# Statemachine_ST7735.net
KiCad netlist of a schematic drawn in EAGLE
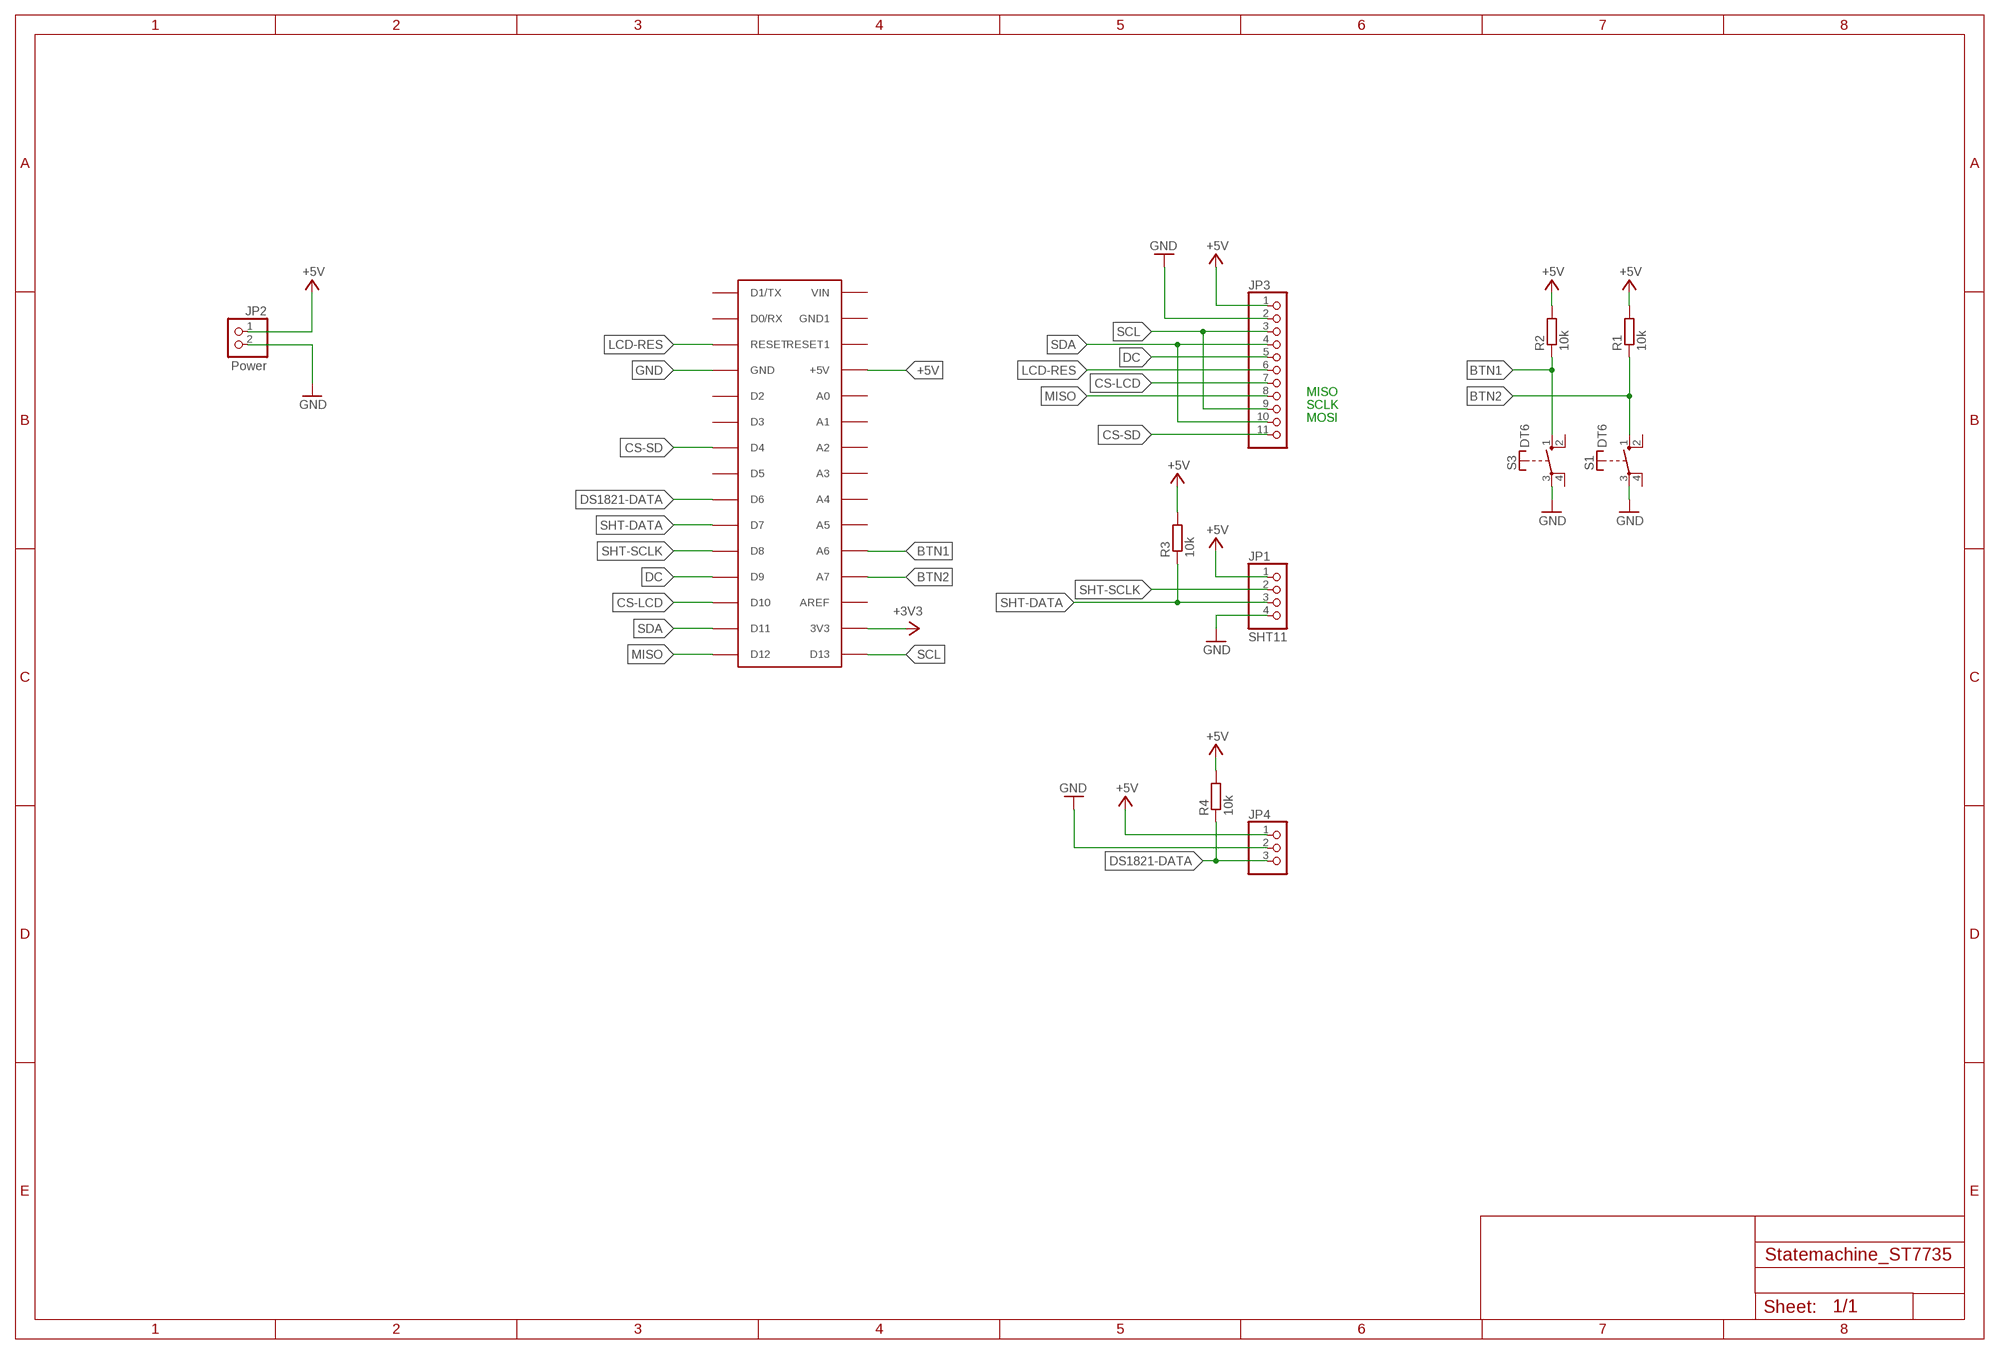
[diagram p0: schematic, sheet 1]

(export (version "E")
  (design (tool "Eeschema 10.0.6"))
  (components
    (comp (ref "JP1")
      (value "SHT11")
      (footprint "eagle-import:1X04")
      (libsource (lib "eagle-import") (part "PINHD-1X4"))
    )
    (comp (ref "JP2")
      (value "Power")
      (footprint "eagle-import:1X02")
      (libsource (lib "eagle-import") (part "PINHD-1X2"))
    )
    (comp (ref "JP3")
      (value "PINHD-1X11")
      (footprint "eagle-import:1X11")
      (libsource (lib "eagle-import") (part "PINHD-1X11"))
    )
    (comp (ref "JP4")
      (value "PINHD-1X3")
      (footprint "eagle-import:1X03")
      (libsource (lib "eagle-import") (part "PINHD-1X3"))
    )
    (comp (ref "R1")
      (value "10k")
      (footprint "eagle-import:0207_10")
      (libsource (lib "eagle-import") (part "R-EU_0207/10"))
    )
    (comp (ref "R2")
      (value "10k")
      (footprint "eagle-import:0204_7")
      (libsource (lib "eagle-import") (part "R-EU_0204/7"))
    )
    (comp (ref "R3")
      (value "10k")
      (footprint "eagle-import:0204_7")
      (libsource (lib "eagle-import") (part "R-EU_0204/7"))
    )
    (comp (ref "R4")
      (value "10k")
      (footprint "eagle-import:0207_10")
      (libsource (lib "eagle-import") (part "R-EU_0207/10"))
    )
    (comp (ref "S1")
      (value "DT6")
      (footprint "eagle-import:DT6")
      (libsource (lib "eagle-import") (part "DT6"))
    )
    (comp (ref "S3")
      (value "DT6")
      (footprint "eagle-import:DT6")
      (libsource (lib "eagle-import") (part "DT6"))
    )
    (comp (ref "U$1")
      (value "ARDUINONANO")
      (footprint "eagle-import:PDIP-32")
      (libsource (lib "eagle-import") (part "ARDUINONANO"))
    )
  )
  (nets
    (net (code "1") (name "+3V3") (class "Default")
      (node (ref "U$1") (pin "3V3") (pinfunction "3V3_3V3") (pintype "bidirectional"))
    )
    (net (code "2") (name "+5V") (class "Default")
      (node (ref "JP1") (pin "1") (pinfunction "1_1") (pintype "passive"))
      (node (ref "JP2") (pin "1") (pinfunction "1_1") (pintype "passive"))
      (node (ref "JP3") (pin "1") (pinfunction "1_1") (pintype "passive"))
      (node (ref "JP4") (pin "1") (pinfunction "1_1") (pintype "passive"))
      (node (ref "R1") (pin "2") (pinfunction "2_2") (pintype "passive"))
      (node (ref "R2") (pin "2") (pinfunction "2_2") (pintype "passive"))
      (node (ref "R3") (pin "2") (pinfunction "2_2") (pintype "passive"))
      (node (ref "R4") (pin "2") (pinfunction "2_2") (pintype "passive"))
      (node (ref "U$1") (pin "+5V") (pinfunction "+5V_+5V") (pintype "bidirectional"))
    )
    (net (code "3") (name "BTN1") (class "Default")
      (node (ref "R2") (pin "1") (pinfunction "1_1") (pintype "passive"))
      (node (ref "S3") (pin "1") (pinfunction "S_1") (pintype "passive"))
      (node (ref "U$1") (pin "A6") (pinfunction "A6_A6") (pintype "bidirectional"))
    )
    (net (code "4") (name "BTN2") (class "Default")
      (node (ref "R1") (pin "1") (pinfunction "1_1") (pintype "passive"))
      (node (ref "S1") (pin "1") (pinfunction "S_1") (pintype "passive"))
      (node (ref "U$1") (pin "A7") (pinfunction "A7_A7") (pintype "bidirectional"))
    )
    (net (code "5") (name "CS-LCD") (class "Default")
      (node (ref "JP3") (pin "7") (pinfunction "7_7") (pintype "passive"))
      (node (ref "U$1") (pin "D10") (pinfunction "D10_D10") (pintype "bidirectional"))
    )
    (net (code "6") (name "CS-SD") (class "Default")
      (node (ref "JP3") (pin "11") (pinfunction "11_11") (pintype "passive"))
      (node (ref "U$1") (pin "D4") (pinfunction "D4_D4") (pintype "bidirectional"))
    )
    (net (code "7") (name "DC") (class "Default")
      (node (ref "JP3") (pin "5") (pinfunction "5_5") (pintype "passive"))
      (node (ref "U$1") (pin "D9") (pinfunction "D9_D9") (pintype "bidirectional"))
    )
    (net (code "8") (name "DS1821-DATA") (class "Default")
      (node (ref "JP4") (pin "3") (pinfunction "3_3") (pintype "passive"))
      (node (ref "R4") (pin "1") (pinfunction "1_1") (pintype "passive"))
      (node (ref "U$1") (pin "D6") (pinfunction "D6_D6") (pintype "bidirectional"))
    )
    (net (code "9") (name "GND") (class "Default")
      (node (ref "JP1") (pin "4") (pinfunction "4_4") (pintype "passive"))
      (node (ref "JP2") (pin "2") (pinfunction "2_2") (pintype "passive"))
      (node (ref "JP3") (pin "2") (pinfunction "2_2") (pintype "passive"))
      (node (ref "JP4") (pin "2") (pinfunction "2_2") (pintype "passive"))
      (node (ref "S1") (pin "3") (pinfunction "P_3") (pintype "passive"))
      (node (ref "S3") (pin "3") (pinfunction "P_3") (pintype "passive"))
      (node (ref "U$1") (pin "GND") (pinfunction "GND_GND") (pintype "bidirectional"))
    )
    (net (code "10") (name "LCD-RES") (class "Default")
      (node (ref "JP3") (pin "6") (pinfunction "6_6") (pintype "passive"))
      (node (ref "U$1") (pin "RESET") (pinfunction "RESET_RESET") (pintype "bidirectional"))
    )
    (net (code "11") (name "MISO") (class "Default")
      (node (ref "JP3") (pin "8") (pinfunction "8_8") (pintype "passive"))
      (node (ref "U$1") (pin "D12") (pinfunction "D12_D12") (pintype "bidirectional"))
    )
    (net (code "12") (name "SCL") (class "Default")
      (node (ref "JP3") (pin "3") (pinfunction "3_3") (pintype "passive"))
      (node (ref "JP3") (pin "9") (pinfunction "9_9") (pintype "passive"))
      (node (ref "U$1") (pin "D13") (pinfunction "D13_D13") (pintype "bidirectional"))
    )
    (net (code "13") (name "SDA") (class "Default")
      (node (ref "JP3") (pin "10") (pinfunction "10_10") (pintype "passive"))
      (node (ref "JP3") (pin "4") (pinfunction "4_4") (pintype "passive"))
      (node (ref "U$1") (pin "D11") (pinfunction "D11_D11") (pintype "bidirectional"))
    )
    (net (code "14") (name "SHT-DATA") (class "Default")
      (node (ref "JP1") (pin "3") (pinfunction "3_3") (pintype "passive"))
      (node (ref "R3") (pin "1") (pinfunction "1_1") (pintype "passive"))
      (node (ref "U$1") (pin "D7") (pinfunction "D7_D7") (pintype "bidirectional"))
    )
    (net (code "15") (name "SHT-SCLK") (class "Default")
      (node (ref "JP1") (pin "2") (pinfunction "2_2") (pintype "passive"))
      (node (ref "U$1") (pin "D8") (pinfunction "D8_D8") (pintype "bidirectional"))
    )
    (net (code "16") (name "unconnected-(S1-P-Pad4)") (class "Default")
      (node (ref "S1") (pin "4") (pinfunction "P_4") (pintype "passive"))
    )
    (net (code "17") (name "unconnected-(S1-S-Pad2)") (class "Default")
      (node (ref "S1") (pin "2") (pinfunction "S_2") (pintype "passive"))
    )
    (net (code "18") (name "unconnected-(S3-P-Pad4)") (class "Default")
      (node (ref "S3") (pin "4") (pinfunction "P_4") (pintype "passive"))
    )
    (net (code "19") (name "unconnected-(S3-S-Pad2)") (class "Default")
      (node (ref "S3") (pin "2") (pinfunction "S_2") (pintype "passive"))
    )
    (net (code "20") (name "unconnected-(U$1-PadA0)") (class "Default")
      (node (ref "U$1") (pin "A0") (pinfunction "A0_A0") (pintype "bidirectional"))
    )
    (net (code "21") (name "unconnected-(U$1-PadA1)") (class "Default")
      (node (ref "U$1") (pin "A1") (pinfunction "A1_A1") (pintype "bidirectional"))
    )
    (net (code "22") (name "unconnected-(U$1-PadA2)") (class "Default")
      (node (ref "U$1") (pin "A2") (pinfunction "A2_A2") (pintype "bidirectional"))
    )
    (net (code "23") (name "unconnected-(U$1-PadA3)") (class "Default")
      (node (ref "U$1") (pin "A3") (pinfunction "A3_A3") (pintype "bidirectional"))
    )
    (net (code "24") (name "unconnected-(U$1-PadA4)") (class "Default")
      (node (ref "U$1") (pin "A4") (pinfunction "A4_A4") (pintype "bidirectional"))
    )
    (net (code "25") (name "unconnected-(U$1-PadA5)") (class "Default")
      (node (ref "U$1") (pin "A5") (pinfunction "A5_A5") (pintype "bidirectional"))
    )
    (net (code "26") (name "unconnected-(U$1-PadAREF)") (class "Default")
      (node (ref "U$1") (pin "AREF") (pinfunction "AREF_AREF") (pintype "bidirectional"))
    )
    (net (code "27") (name "unconnected-(U$1-PadD0{slash}RX)") (class "Default")
      (node (ref "U$1") (pin "D0/RX") (pinfunction "D0/RX_D0/RX") (pintype "bidirectional"))
    )
    (net (code "28") (name "unconnected-(U$1-PadD1{slash}TX)") (class "Default")
      (node (ref "U$1") (pin "D1/TX") (pinfunction "D1/TX_D1/TX") (pintype "bidirectional"))
    )
    (net (code "29") (name "unconnected-(U$1-PadD2)") (class "Default")
      (node (ref "U$1") (pin "D2") (pinfunction "D2_D2") (pintype "bidirectional"))
    )
    (net (code "30") (name "unconnected-(U$1-PadD3)") (class "Default")
      (node (ref "U$1") (pin "D3") (pinfunction "D3_D3") (pintype "bidirectional"))
    )
    (net (code "31") (name "unconnected-(U$1-PadD5)") (class "Default")
      (node (ref "U$1") (pin "D5") (pinfunction "D5_D5") (pintype "bidirectional"))
    )
    (net (code "32") (name "unconnected-(U$1-PadGND1)") (class "Default")
      (node (ref "U$1") (pin "GND1") (pinfunction "GND1_GND1") (pintype "bidirectional"))
    )
    (net (code "33") (name "unconnected-(U$1-PadRESET1)") (class "Default")
      (node (ref "U$1") (pin "RESET1") (pinfunction "RESET1_RESET1") (pintype "bidirectional"))
    )
    (net (code "34") (name "unconnected-(U$1-PadVIN)") (class "Default")
      (node (ref "U$1") (pin "VIN") (pinfunction "VIN_VIN") (pintype "bidirectional"))
    )
  )
)
